# io-pack-3-1.net
KiCad netlist of a schematic drawn in EAGLE
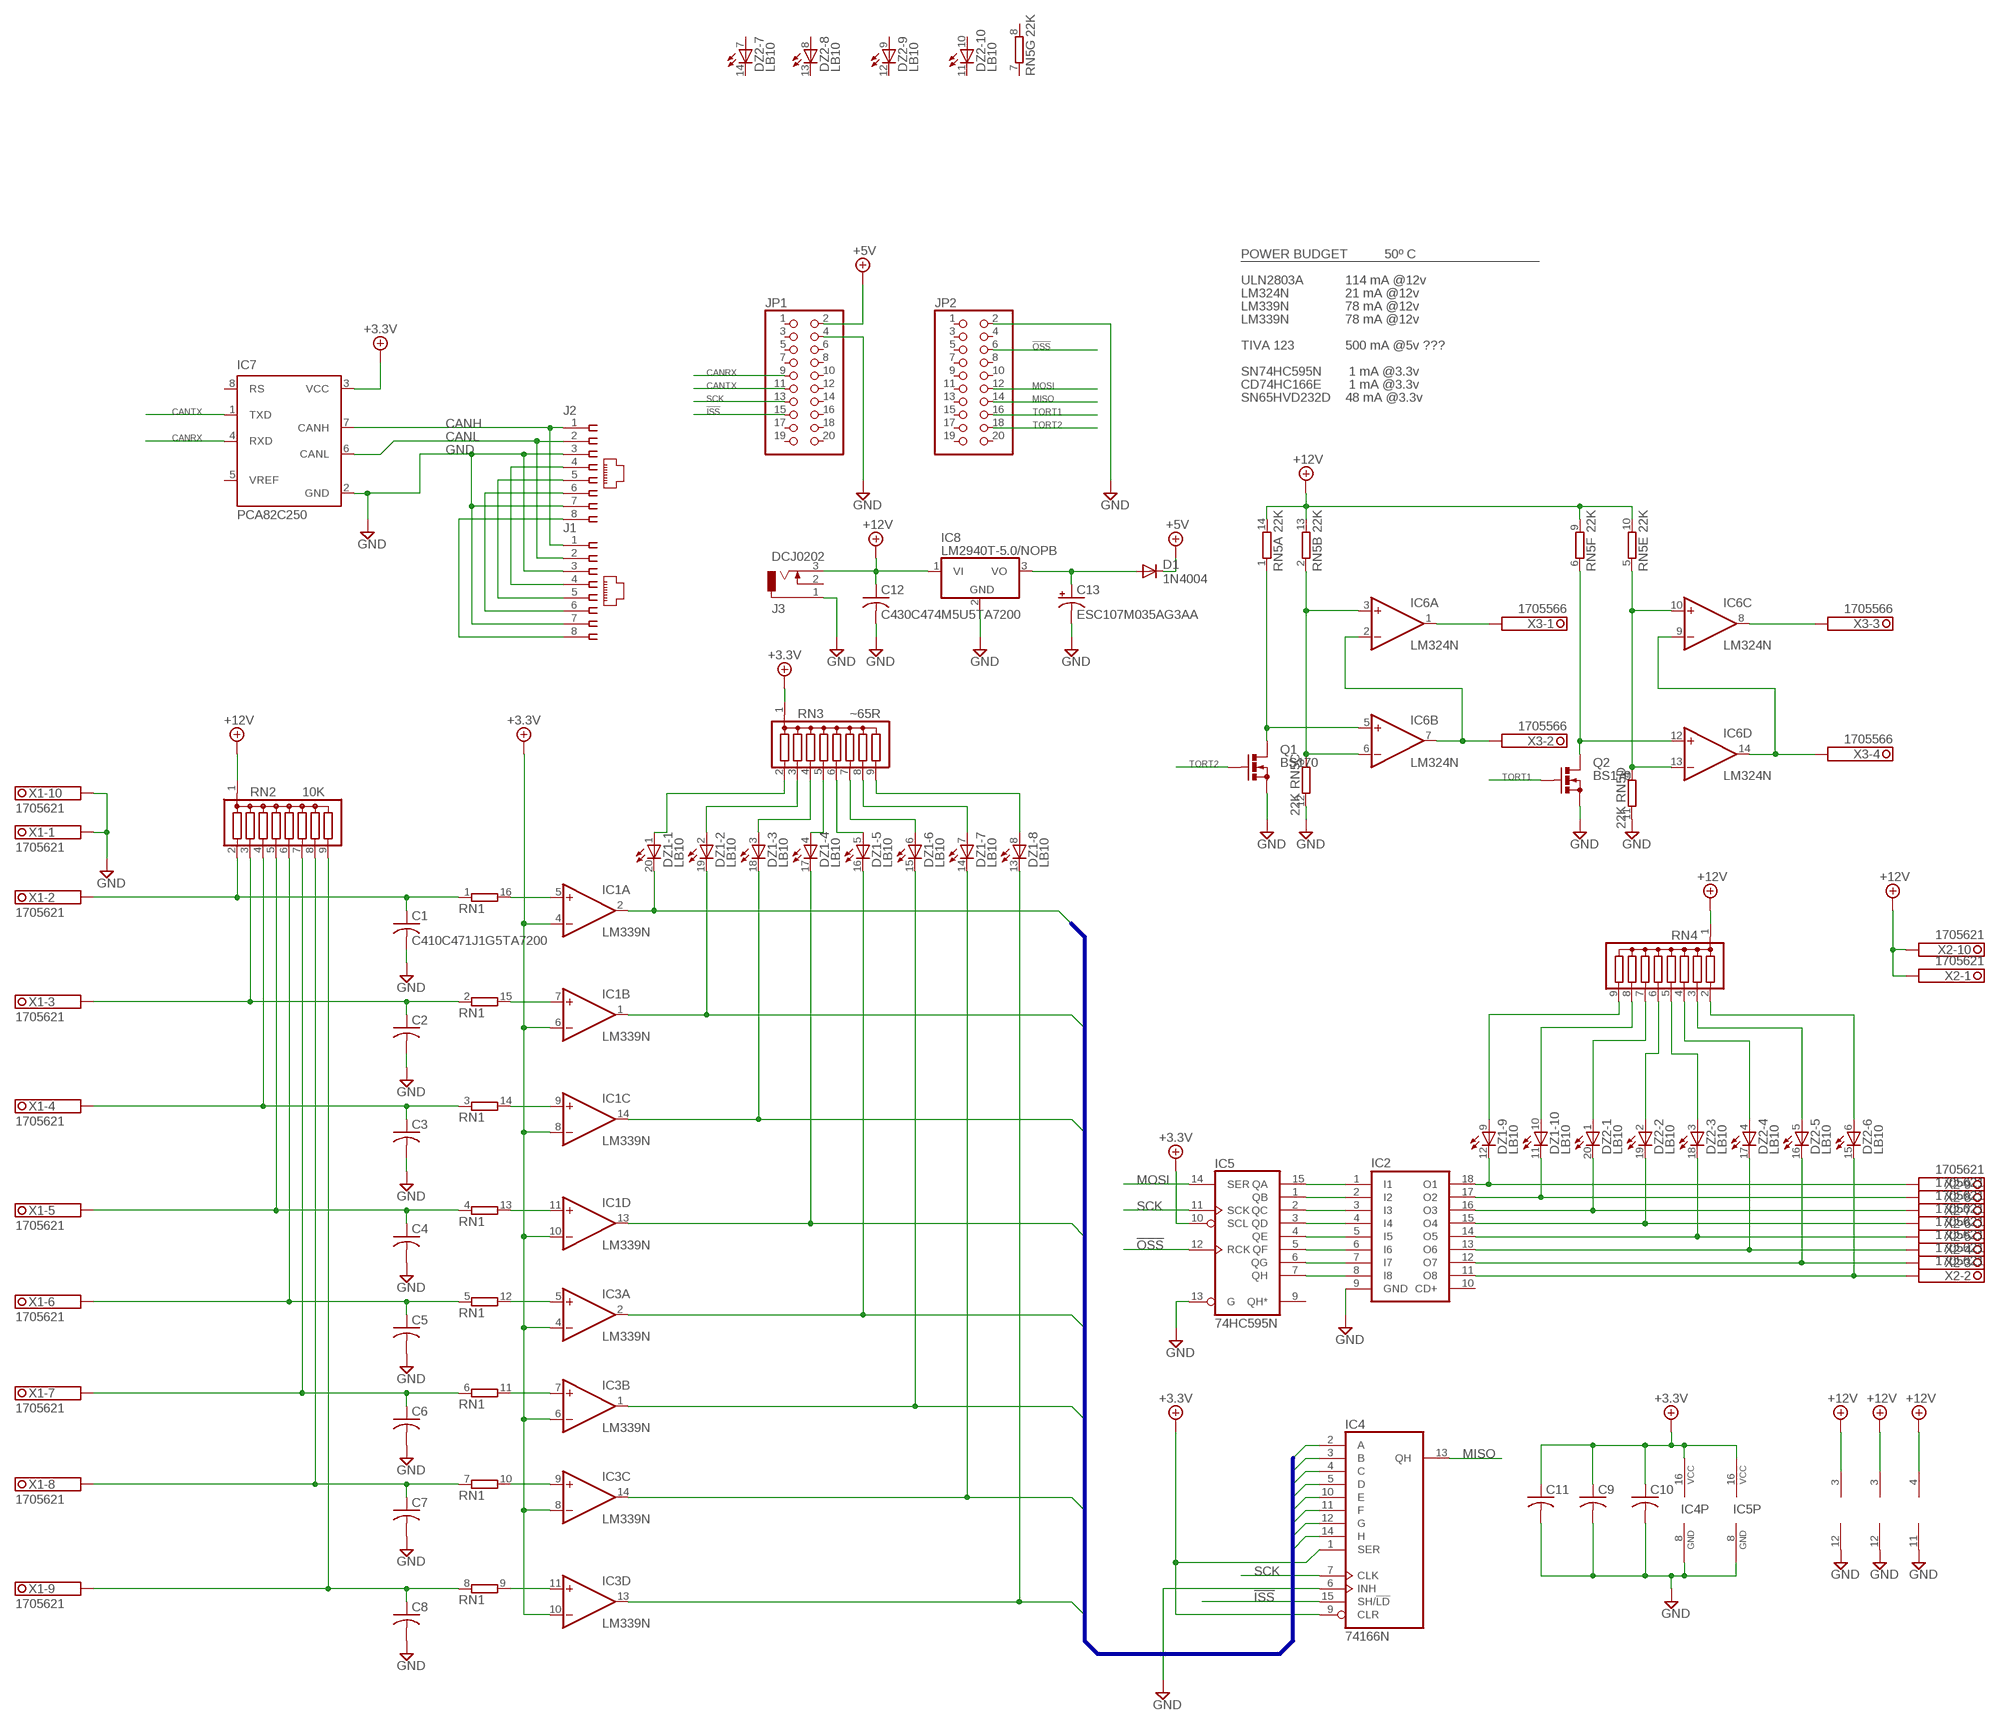
[diagram p0: schematic, sheet 1]

(export (version "E")
  (design (tool "Eeschema 10.0.6"))
  (components
    (comp (ref "C1")
      (value "C410C471J1G5TA7200")
      (footprint "eagle-import:C050-025X075")
      (libsource (lib "eagle-import") (part "C-US050-025X075"))
    )
    (comp (ref "C2")
      (value "C-US050-025X075")
      (footprint "eagle-import:C050-025X075")
      (libsource (lib "eagle-import") (part "C-US050-025X075"))
    )
    (comp (ref "C3")
      (value "C-US050-025X075")
      (footprint "eagle-import:C050-025X075")
      (libsource (lib "eagle-import") (part "C-US050-025X075"))
    )
    (comp (ref "C4")
      (value "C-US050-025X075")
      (footprint "eagle-import:C050-025X075")
      (libsource (lib "eagle-import") (part "C-US050-025X075"))
    )
    (comp (ref "C5")
      (value "C-US050-025X075")
      (footprint "eagle-import:C050-025X075")
      (libsource (lib "eagle-import") (part "C-US050-025X075"))
    )
    (comp (ref "C6")
      (value "C-US050-025X075")
      (footprint "eagle-import:C050-025X075")
      (libsource (lib "eagle-import") (part "C-US050-025X075"))
    )
    (comp (ref "C7")
      (value "C-US050-025X075")
      (footprint "eagle-import:C050-025X075")
      (libsource (lib "eagle-import") (part "C-US050-025X075"))
    )
    (comp (ref "C8")
      (value "C-US050-025X075")
      (footprint "eagle-import:C050-025X075")
      (libsource (lib "eagle-import") (part "C-US050-025X075"))
    )
    (comp (ref "C9")
      (value "C-US050-025X075")
      (footprint "eagle-import:C050-025X075")
      (libsource (lib "eagle-import") (part "C-US050-025X075"))
    )
    (comp (ref "C10")
      (value "C-US050-025X075")
      (footprint "eagle-import:C050-025X075")
      (libsource (lib "eagle-import") (part "C-US050-025X075"))
    )
    (comp (ref "C11")
      (value "C-US050-025X075")
      (footprint "eagle-import:C050-025X075")
      (libsource (lib "eagle-import") (part "C-US050-025X075"))
    )
    (comp (ref "C12")
      (value "C430C474M5U5TA7200")
      (footprint "eagle-import:C075-032X103")
      (libsource (lib "eagle-import") (part "C-US075-032X103"))
    )
    (comp (ref "C13")
      (value "ESC107M035AG3AA")
      (footprint "eagle-import:E3,5-8")
      (libsource (lib "eagle-import") (part "CPOL-USE3.5-8"))
    )
    (comp (ref "D1")
      (value "1N4004")
      (footprint "eagle-import:DO41-10")
      (libsource (lib "eagle-import") (part "1N4004"))
    )
    (comp (ref "DZ1")
      (value "LB10")
      (footprint "eagle-import:LB10")
      (libsource (lib "eagle-import") (part "LB10"))
    )
    (comp (ref "DZ2")
      (value "LB10")
      (footprint "eagle-import:LB10")
      (libsource (lib "eagle-import") (part "LB10"))
    )
    (comp (ref "IC1")
      (value "LM339N")
      (footprint "eagle-import:DIL14")
      (libsource (lib "eagle-import") (part "LM339N"))
    )
    (comp (ref "IC2")
      (value "ULN2803A")
      (footprint "eagle-import:DIL18")
      (libsource (lib "eagle-import") (part "ULN2803A"))
    )
    (comp (ref "IC3")
      (value "LM339N")
      (footprint "eagle-import:DIL14")
      (libsource (lib "eagle-import") (part "LM339N"))
    )
    (comp (ref "IC4")
      (value "74166N")
      (footprint "eagle-import:DIL16")
      (libsource (lib "eagle-import") (part "74166N"))
    )
    (comp (ref "IC5")
      (value "74HC595N")
      (footprint "eagle-import:DIL16")
      (libsource (lib "eagle-import") (part "74595NLS"))
    )
    (comp (ref "IC6")
      (value "LM324N")
      (footprint "eagle-import:DIL14")
      (libsource (lib "eagle-import") (part "LM324N"))
    )
    (comp (ref "IC7")
      (value "PCA82C250")
      (footprint "eagle-import:DIL08")
      (libsource (lib "eagle-import") (part "PCA82C250"))
    )
    (comp (ref "IC8")
      (value "LM2940T-5.0/NOPB")
      (footprint "eagle-import:TO220V")
      (libsource (lib "eagle-import") (part "78TV05"))
    )
    (comp (ref "J1")
      (value "555164-1")
      (footprint "eagle-import:555164-1")
      (libsource (lib "eagle-import") (part "555164-1"))
    )
    (comp (ref "J2")
      (value "555164-1")
      (footprint "eagle-import:555164-1")
      (libsource (lib "eagle-import") (part "555164-1"))
    )
    (comp (ref "J3")
      (value "DCJ0202")
      (footprint "eagle-import:DCJ0202")
      (libsource (lib "eagle-import") (part "DCJ0202"))
    )
    (comp (ref "JP1")
      (value "PINHD-2X10")
      (footprint "eagle-import:2X10")
      (libsource (lib "eagle-import") (part "PINHD-2X10"))
    )
    (comp (ref "JP2")
      (value "PINHD-2X10")
      (footprint "eagle-import:2X10")
      (libsource (lib "eagle-import") (part "PINHD-2X10"))
    )
    (comp (ref "Q1")
      (value "BS170")
      (footprint "eagle-import:SOT54E")
      (libsource (lib "eagle-import") (part "BS170"))
    )
    (comp (ref "Q2")
      (value "BS170")
      (footprint "eagle-import:SOT54E")
      (libsource (lib "eagle-import") (part "BS170"))
    )
    (comp (ref "RN1")
      (value "8R-P")
      (footprint "eagle-import:DIL16")
      (libsource (lib "eagle-import") (part "8R-P"))
    )
    (comp (ref "RN2")
      (value "10K")
      (footprint "eagle-import:SIL9")
      (libsource (lib "eagle-import") (part "G08R"))
    )
    (comp (ref "RN3")
      (value "~65R")
      (footprint "eagle-import:SIL9")
      (libsource (lib "eagle-import") (part "G08R"))
    )
    (comp (ref "RN4")
      (value "G08R")
      (footprint "eagle-import:SIL9")
      (libsource (lib "eagle-import") (part "G08R"))
    )
    (comp (ref "RN5")
      (value "22K")
      (footprint "eagle-import:DIL14")
      (libsource (lib "eagle-import") (part "7R-N"))
    )
    (comp (ref "X1")
      (value "1705621")
      (footprint "eagle-import:1705621")
      (libsource (lib "eagle-import") (part "1705621"))
    )
    (comp (ref "X2")
      (value "1705621")
      (footprint "eagle-import:1705621")
      (libsource (lib "eagle-import") (part "1705621"))
    )
    (comp (ref "X3")
      (value "1705566")
      (footprint "eagle-import:1705566")
      (libsource (lib "eagle-import") (part "1705566"))
    )
  )
  (nets
    (net (code "1") (name "+3.3V") (class "Default")
      (node (ref "C10") (pin "1") (pinfunction "1_1") (pintype "passive"))
      (node (ref "C11") (pin "1") (pinfunction "1_1") (pintype "passive"))
      (node (ref "C9") (pin "1") (pinfunction "1_1") (pintype "passive"))
      (node (ref "IC1") (pin "10") (pinfunction "-IN_10") (pintype "input"))
      (node (ref "IC1") (pin "4") (pinfunction "-IN_4") (pintype "input"))
      (node (ref "IC1") (pin "6") (pinfunction "-IN_6") (pintype "input"))
      (node (ref "IC1") (pin "8") (pinfunction "-IN_8") (pintype "input"))
      (node (ref "IC3") (pin "10") (pinfunction "-IN_10") (pintype "input"))
      (node (ref "IC3") (pin "4") (pinfunction "-IN_4") (pintype "input"))
      (node (ref "IC3") (pin "6") (pinfunction "-IN_6") (pintype "input"))
      (node (ref "IC3") (pin "8") (pinfunction "-IN_8") (pintype "input"))
      (node (ref "IC4") (pin "1") (pinfunction "SER_1") (pintype "input"))
      (node (ref "IC4") (pin "16") (pinfunction "VCC_16") (pintype "power_in"))
      (node (ref "IC4") (pin "9") (pinfunction "CLR_9") (pintype "input"))
      (node (ref "IC5") (pin "10") (pinfunction "SCL_10") (pintype "input"))
      (node (ref "IC5") (pin "16") (pinfunction "VCC_16") (pintype "power_in"))
      (node (ref "IC7") (pin "3") (pinfunction "VCC_3") (pintype "power_in"))
      (node (ref "RN3") (pin "1") (pinfunction "1_1") (pintype "passive"))
    )
    (net (code "2") (name "+5V") (class "Default")
      (node (ref "D1") (pin "C") (pinfunction "C_C") (pintype "passive"))
      (node (ref "JP1") (pin "2") (pinfunction "2_2") (pintype "passive"))
    )
    (net (code "3") (name "+12V") (class "Default")
      (node (ref "C12") (pin "1") (pinfunction "1_1") (pintype "passive"))
      (node (ref "IC1") (pin "3") (pinfunction "V+_3") (pintype "power_in"))
      (node (ref "IC3") (pin "3") (pinfunction "V+_3") (pintype "power_in"))
      (node (ref "IC6") (pin "4") (pinfunction "V+_4") (pintype "power_in"))
      (node (ref "IC8") (pin "1") (pinfunction "VI_1") (pintype "input"))
      (node (ref "J3") (pin "3") (pinfunction "3_3") (pintype "passive"))
      (node (ref "RN2") (pin "1") (pinfunction "1_1") (pintype "passive"))
      (node (ref "RN4") (pin "1") (pinfunction "1_1") (pintype "passive"))
      (node (ref "RN5") (pin "10") (pinfunction "2_10") (pintype "passive"))
      (node (ref "RN5") (pin "13") (pinfunction "2_13") (pintype "passive"))
      (node (ref "RN5") (pin "14") (pinfunction "2_14") (pintype "passive"))
      (node (ref "RN5") (pin "9") (pinfunction "2_9") (pintype "passive"))
      (node (ref "X2") (pin "1.1") (pinfunction "1A_1.1") (pintype "passive"))
      (node (ref "X2") (pin "1.2") (pinfunction "1A_1.2") (pintype "passive"))
      (node (ref "X2") (pin "10.1") (pinfunction "1A_10.1") (pintype "passive"))
      (node (ref "X2") (pin "10.2") (pinfunction "1A_10.2") (pintype "passive"))
    )
    (net (code "4") (name "/CANH") (class "Default")
      (node (ref "IC7") (pin "7") (pinfunction "CANH_7") (pintype "bidirectional"))
      (node (ref "J1") (pin "1") (pinfunction "1_1") (pintype "passive"))
      (node (ref "J2") (pin "1") (pinfunction "1_1") (pintype "passive"))
    )
    (net (code "5") (name "/CANL") (class "Default")
      (node (ref "IC7") (pin "6") (pinfunction "CANL_6") (pintype "bidirectional"))
      (node (ref "J1") (pin "2") (pinfunction "2_2") (pintype "passive"))
      (node (ref "J2") (pin "2") (pinfunction "2_2") (pintype "passive"))
    )
    (net (code "6") (name "/CANRX") (class "Default")
      (node (ref "IC7") (pin "4") (pinfunction "RXD_4") (pintype "output"))
      (node (ref "JP1") (pin "9") (pinfunction "9_9") (pintype "passive"))
    )
    (net (code "7") (name "/CANTX") (class "Default")
      (node (ref "IC7") (pin "1") (pinfunction "TXD_1") (pintype "input"))
      (node (ref "JP1") (pin "11") (pinfunction "11_11") (pintype "passive"))
    )
    (net (code "8") (name "/IN0") (class "Default")
      (node (ref "DZ1") (pin "20") (pinfunction "C_20") (pintype "passive"))
      (node (ref "IC1") (pin "2") (pinfunction "OUT_2") (pintype "open_collector"))
      (node (ref "IC4") (pin "2") (pinfunction "A_2") (pintype "input"))
    )
    (net (code "9") (name "/IN1") (class "Default")
      (node (ref "DZ1") (pin "19") (pinfunction "C_19") (pintype "passive"))
      (node (ref "IC1") (pin "1") (pinfunction "OUT_1") (pintype "open_collector"))
      (node (ref "IC4") (pin "3") (pinfunction "B_3") (pintype "input"))
    )
    (net (code "10") (name "/IN2") (class "Default")
      (node (ref "DZ1") (pin "18") (pinfunction "C_18") (pintype "passive"))
      (node (ref "IC1") (pin "14") (pinfunction "OUT_14") (pintype "open_collector"))
      (node (ref "IC4") (pin "4") (pinfunction "C_4") (pintype "input"))
    )
    (net (code "11") (name "/IN3") (class "Default")
      (node (ref "DZ1") (pin "17") (pinfunction "C_17") (pintype "passive"))
      (node (ref "IC1") (pin "13") (pinfunction "OUT_13") (pintype "open_collector"))
      (node (ref "IC4") (pin "5") (pinfunction "D_5") (pintype "input"))
    )
    (net (code "12") (name "/IN4") (class "Default")
      (node (ref "DZ1") (pin "16") (pinfunction "C_16") (pintype "passive"))
      (node (ref "IC3") (pin "2") (pinfunction "OUT_2") (pintype "open_collector"))
      (node (ref "IC4") (pin "10") (pinfunction "E_10") (pintype "input"))
    )
    (net (code "13") (name "/IN5") (class "Default")
      (node (ref "DZ1") (pin "15") (pinfunction "C_15") (pintype "passive"))
      (node (ref "IC3") (pin "1") (pinfunction "OUT_1") (pintype "open_collector"))
      (node (ref "IC4") (pin "11") (pinfunction "F_11") (pintype "input"))
    )
    (net (code "14") (name "/IN6") (class "Default")
      (node (ref "DZ1") (pin "14") (pinfunction "C_14") (pintype "passive"))
      (node (ref "IC3") (pin "14") (pinfunction "OUT_14") (pintype "open_collector"))
      (node (ref "IC4") (pin "12") (pinfunction "G_12") (pintype "input"))
    )
    (net (code "15") (name "/IN7") (class "Default")
      (node (ref "DZ1") (pin "13") (pinfunction "C_13") (pintype "passive"))
      (node (ref "IC3") (pin "13") (pinfunction "OUT_13") (pintype "open_collector"))
      (node (ref "IC4") (pin "14") (pinfunction "H_14") (pintype "input"))
    )
    (net (code "16") (name "/MISO") (class "Default")
      (node (ref "IC4") (pin "13") (pinfunction "QH_13") (pintype "output"))
      (node (ref "JP2") (pin "14") (pinfunction "14_14") (pintype "passive"))
    )
    (net (code "17") (name "/MOSI") (class "Default")
      (node (ref "IC5") (pin "14") (pinfunction "SER_14") (pintype "input"))
      (node (ref "JP2") (pin "12") (pinfunction "12_12") (pintype "passive"))
    )
    (net (code "18") (name "/SCK") (class "Default")
      (node (ref "IC4") (pin "7") (pinfunction "CLK_7") (pintype "input"))
      (node (ref "IC5") (pin "11") (pinfunction "SCK_11") (pintype "input"))
      (node (ref "JP1") (pin "13") (pinfunction "13_13") (pintype "passive"))
    )
    (net (code "19") (name "/TORT1") (class "Default")
      (node (ref "JP2") (pin "16") (pinfunction "16_16") (pintype "passive"))
      (node (ref "Q2") (pin "G") (pinfunction "G_G") (pintype "passive"))
    )
    (net (code "20") (name "/TORT2") (class "Default")
      (node (ref "JP2") (pin "18") (pinfunction "18_18") (pintype "passive"))
      (node (ref "Q1") (pin "G") (pinfunction "G_G") (pintype "passive"))
    )
    (net (code "21") (name "/~{ISS}") (class "Default")
      (node (ref "IC4") (pin "15") (pinfunction "SH/~{LD}_15") (pintype "input"))
      (node (ref "JP1") (pin "15") (pinfunction "15_15") (pintype "passive"))
    )
    (net (code "22") (name "/~{OSS}") (class "Default")
      (node (ref "IC5") (pin "12") (pinfunction "RCK_12") (pintype "input"))
      (node (ref "JP2") (pin "6") (pinfunction "6_6") (pintype "passive"))
    )
    (net (code "23") (name "GND") (class "Default")
      (node (ref "C1") (pin "2") (pinfunction "2_2") (pintype "passive"))
      (node (ref "C10") (pin "2") (pinfunction "2_2") (pintype "passive"))
      (node (ref "C11") (pin "2") (pinfunction "2_2") (pintype "passive"))
      (node (ref "C12") (pin "2") (pinfunction "2_2") (pintype "passive"))
      (node (ref "C13") (pin "-") (pinfunction "-_-") (pintype "passive"))
      (node (ref "C2") (pin "2") (pinfunction "2_2") (pintype "passive"))
      (node (ref "C3") (pin "2") (pinfunction "2_2") (pintype "passive"))
      (node (ref "C4") (pin "2") (pinfunction "2_2") (pintype "passive"))
      (node (ref "C5") (pin "2") (pinfunction "2_2") (pintype "passive"))
      (node (ref "C6") (pin "2") (pinfunction "2_2") (pintype "passive"))
      (node (ref "C7") (pin "2") (pinfunction "2_2") (pintype "passive"))
      (node (ref "C8") (pin "2") (pinfunction "2_2") (pintype "passive"))
      (node (ref "C9") (pin "2") (pinfunction "2_2") (pintype "passive"))
      (node (ref "IC1") (pin "12") (pinfunction "GND_12") (pintype "power_in"))
      (node (ref "IC2") (pin "9") (pinfunction "GND_9") (pintype "power_in"))
      (node (ref "IC3") (pin "12") (pinfunction "GND_12") (pintype "power_in"))
      (node (ref "IC4") (pin "6") (pinfunction "INH_6") (pintype "input"))
      (node (ref "IC4") (pin "8") (pinfunction "GND_8") (pintype "power_in"))
      (node (ref "IC5") (pin "13") (pinfunction "G_13") (pintype "input"))
      (node (ref "IC5") (pin "8") (pinfunction "GND_8") (pintype "power_in"))
      (node (ref "IC6") (pin "11") (pinfunction "V-_11") (pintype "power_in"))
      (node (ref "IC7") (pin "2") (pinfunction "GND_2") (pintype "power_in"))
      (node (ref "IC8") (pin "2") (pinfunction "GND_2") (pintype "passive"))
      (node (ref "J1") (pin "3") (pinfunction "3_3") (pintype "passive"))
      (node (ref "J1") (pin "7") (pinfunction "7_7") (pintype "passive"))
      (node (ref "J2") (pin "3") (pinfunction "3_3") (pintype "passive"))
      (node (ref "J2") (pin "7") (pinfunction "7_7") (pintype "passive"))
      (node (ref "J3") (pin "1") (pinfunction "1_1") (pintype "passive"))
      (node (ref "JP1") (pin "4") (pinfunction "4_4") (pintype "passive"))
      (node (ref "JP2") (pin "2") (pinfunction "2_2") (pintype "passive"))
      (node (ref "Q1") (pin "S") (pinfunction "S_S") (pintype "passive"))
      (node (ref "Q2") (pin "S") (pinfunction "S_S") (pintype "passive"))
      (node (ref "RN5") (pin "11") (pinfunction "2_11") (pintype "passive"))
      (node (ref "RN5") (pin "12") (pinfunction "2_12") (pintype "passive"))
      (node (ref "X1") (pin "1.1") (pinfunction "1A_1.1") (pintype "passive"))
      (node (ref "X1") (pin "1.2") (pinfunction "1A_1.2") (pintype "passive"))
      (node (ref "X1") (pin "10.1") (pinfunction "1A_10.1") (pintype "passive"))
      (node (ref "X1") (pin "10.2") (pinfunction "1A_10.2") (pintype "passive"))
    )
    (net (code "24") (name "Net-(C1-Pad1)") (class "Default")
      (node (ref "C1") (pin "1") (pinfunction "1_1") (pintype "passive"))
      (node (ref "RN1") (pin "1") (pinfunction "1_1") (pintype "passive"))
      (node (ref "RN2") (pin "2") (pinfunction "2_2") (pintype "passive"))
      (node (ref "X1") (pin "2.1") (pinfunction "1A_2.1") (pintype "passive"))
      (node (ref "X1") (pin "2.2") (pinfunction "1A_2.2") (pintype "passive"))
    )
    (net (code "25") (name "Net-(DZ1A-A)") (class "Default")
      (node (ref "DZ1") (pin "1") (pinfunction "A_1") (pintype "passive"))
      (node (ref "RN3") (pin "2") (pinfunction "2_2") (pintype "passive"))
    )
    (net (code "26") (name "Net-(DZ1B-A)") (class "Default")
      (node (ref "DZ1") (pin "10") (pinfunction "A_10") (pintype "passive"))
      (node (ref "RN4") (pin "8") (pinfunction "8_8") (pintype "passive"))
    )
    (net (code "27") (name "Net-(DZ1B-C)") (class "Default")
      (node (ref "DZ1") (pin "11") (pinfunction "C_11") (pintype "passive"))
      (node (ref "IC2") (pin "17") (pinfunction "O2_17") (pintype "open_collector"))
      (node (ref "X2") (pin "8.1") (pinfunction "1A_8.1") (pintype "passive"))
      (node (ref "X2") (pin "8.2") (pinfunction "1A_8.2") (pintype "passive"))
    )
    (net (code "28") (name "Net-(DZ1C-A)") (class "Default")
      (node (ref "DZ1") (pin "2") (pinfunction "A_2") (pintype "passive"))
      (node (ref "RN3") (pin "3") (pinfunction "3_3") (pintype "passive"))
    )
    (net (code "29") (name "Net-(DZ1D-A)") (class "Default")
      (node (ref "DZ1") (pin "3") (pinfunction "A_3") (pintype "passive"))
      (node (ref "RN3") (pin "4") (pinfunction "4_4") (pintype "passive"))
    )
    (net (code "30") (name "Net-(DZ1E-A)") (class "Default")
      (node (ref "DZ1") (pin "4") (pinfunction "A_4") (pintype "passive"))
      (node (ref "RN3") (pin "5") (pinfunction "5_5") (pintype "passive"))
    )
    (net (code "31") (name "Net-(DZ1F-A)") (class "Default")
      (node (ref "DZ1") (pin "5") (pinfunction "A_5") (pintype "passive"))
      (node (ref "RN3") (pin "6") (pinfunction "6_6") (pintype "passive"))
    )
    (net (code "32") (name "Net-(DZ1G-A)") (class "Default")
      (node (ref "DZ1") (pin "6") (pinfunction "A_6") (pintype "passive"))
      (node (ref "RN3") (pin "7") (pinfunction "7_7") (pintype "passive"))
    )
    (net (code "33") (name "Net-(DZ1H-A)") (class "Default")
      (node (ref "DZ1") (pin "7") (pinfunction "A_7") (pintype "passive"))
      (node (ref "RN3") (pin "8") (pinfunction "8_8") (pintype "passive"))
    )
    (net (code "34") (name "Net-(DZ1I-A)") (class "Default")
      (node (ref "DZ1") (pin "8") (pinfunction "A_8") (pintype "passive"))
      (node (ref "RN3") (pin "9") (pinfunction "9_9") (pintype "passive"))
    )
    (net (code "35") (name "Net-(DZ1J-A)") (class "Default")
      (node (ref "DZ1") (pin "9") (pinfunction "A_9") (pintype "passive"))
      (node (ref "RN4") (pin "9") (pinfunction "9_9") (pintype "passive"))
    )
    (net (code "36") (name "Net-(DZ1J-C)") (class "Default")
      (node (ref "DZ1") (pin "12") (pinfunction "C_12") (pintype "passive"))
      (node (ref "IC2") (pin "18") (pinfunction "O1_18") (pintype "open_collector"))
      (node (ref "X2") (pin "9.1") (pinfunction "1A_9.1") (pintype "passive"))
      (node (ref "X2") (pin "9.2") (pinfunction "1A_9.2") (pintype "passive"))
    )
    (net (code "37") (name "Net-(DZ2A-A)") (class "Default")
      (node (ref "DZ2") (pin "1") (pinfunction "A_1") (pintype "passive"))
      (node (ref "RN4") (pin "7") (pinfunction "7_7") (pintype "passive"))
    )
    (net (code "38") (name "Net-(DZ2A-C)") (class "Default")
      (node (ref "DZ2") (pin "20") (pinfunction "C_20") (pintype "passive"))
      (node (ref "IC2") (pin "16") (pinfunction "O3_16") (pintype "open_collector"))
      (node (ref "X2") (pin "7.1") (pinfunction "1A_7.1") (pintype "passive"))
      (node (ref "X2") (pin "7.2") (pinfunction "1A_7.2") (pintype "passive"))
    )
    (net (code "39") (name "Net-(DZ2C-A)") (class "Default")
      (node (ref "DZ2") (pin "2") (pinfunction "A_2") (pintype "passive"))
      (node (ref "RN4") (pin "6") (pinfunction "6_6") (pintype "passive"))
    )
    (net (code "40") (name "Net-(DZ2C-C)") (class "Default")
      (node (ref "DZ2") (pin "19") (pinfunction "C_19") (pintype "passive"))
      (node (ref "IC2") (pin "15") (pinfunction "O4_15") (pintype "open_collector"))
      (node (ref "X2") (pin "6.1") (pinfunction "1A_6.1") (pintype "passive"))
      (node (ref "X2") (pin "6.2") (pinfunction "1A_6.2") (pintype "passive"))
    )
    (net (code "41") (name "Net-(DZ2D-A)") (class "Default")
      (node (ref "DZ2") (pin "3") (pinfunction "A_3") (pintype "passive"))
      (node (ref "RN4") (pin "5") (pinfunction "5_5") (pintype "passive"))
    )
    (net (code "42") (name "Net-(DZ2D-C)") (class "Default")
      (node (ref "DZ2") (pin "18") (pinfunction "C_18") (pintype "passive"))
      (node (ref "IC2") (pin "14") (pinfunction "O5_14") (pintype "open_collector"))
      (node (ref "X2") (pin "5.1") (pinfunction "1A_5.1") (pintype "passive"))
      (node (ref "X2") (pin "5.2") (pinfunction "1A_5.2") (pintype "passive"))
    )
    (net (code "43") (name "Net-(DZ2E-A)") (class "Default")
      (node (ref "DZ2") (pin "4") (pinfunction "A_4") (pintype "passive"))
      (node (ref "RN4") (pin "4") (pinfunction "4_4") (pintype "passive"))
    )
    (net (code "44") (name "Net-(DZ2E-C)") (class "Default")
      (node (ref "DZ2") (pin "17") (pinfunction "C_17") (pintype "passive"))
      (node (ref "IC2") (pin "13") (pinfunction "O6_13") (pintype "open_collector"))
      (node (ref "X2") (pin "4.1") (pinfunction "1A_4.1") (pintype "passive"))
      (node (ref "X2") (pin "4.2") (pinfunction "1A_4.2") (pintype "passive"))
    )
    (net (code "45") (name "Net-(DZ2F-A)") (class "Default")
      (node (ref "DZ2") (pin "5") (pinfunction "A_5") (pintype "passive"))
      (node (ref "RN4") (pin "3") (pinfunction "3_3") (pintype "passive"))
    )
    (net (code "46") (name "Net-(DZ2F-C)") (class "Default")
      (node (ref "DZ2") (pin "16") (pinfunction "C_16") (pintype "passive"))
      (node (ref "IC2") (pin "12") (pinfunction "O7_12") (pintype "open_collector"))
      (node (ref "X2") (pin "3.1") (pinfunction "1A_3.1") (pintype "passive"))
      (node (ref "X2") (pin "3.2") (pinfunction "1A_3.2") (pintype "passive"))
    )
    (net (code "47") (name "Net-(DZ2G-A)") (class "Default")
      (node (ref "DZ2") (pin "6") (pinfunction "A_6") (pintype "passive"))
      (node (ref "RN4") (pin "2") (pinfunction "2_2") (pintype "passive"))
    )
    (net (code "48") (name "Net-(DZ2G-C)") (class "Default")
      (node (ref "DZ2") (pin "15") (pinfunction "C_15") (pintype "passive"))
      (node (ref "IC2") (pin "11") (pinfunction "O8_11") (pintype "open_collector"))
      (node (ref "X2") (pin "2.1") (pinfunction "1A_2.1") (pintype "passive"))
      (node (ref "X2") (pin "2.2") (pinfunction "1A_2.2") (pintype "passive"))
    )
    (net (code "49") (name "Net-(IC1A-+IN)") (class "Default")
      (node (ref "IC1") (pin "5") (pinfunction "+IN_5") (pintype "input"))
      (node (ref "RN1") (pin "16") (pinfunction "2_16") (pintype "passive"))
    )
    (net (code "50") (name "Net-(IC1B-+IN)") (class "Default")
      (node (ref "IC1") (pin "7") (pinfunction "+IN_7") (pintype "input"))
      (node (ref "RN1") (pin "15") (pinfunction "2_15") (pintype "passive"))
    )
    (net (code "51") (name "Net-(IC1C-+IN)") (class "Default")
      (node (ref "IC1") (pin "9") (pinfunction "+IN_9") (pintype "input"))
      (node (ref "RN1") (pin "14") (pinfunction "2_14") (pintype "passive"))
    )
    (net (code "52") (name "Net-(IC1D-+IN)") (class "Default")
      (node (ref "IC1") (pin "11") (pinfunction "+IN_11") (pintype "input"))
      (node (ref "RN1") (pin "13") (pinfunction "2_13") (pintype "passive"))
    )
    (net (code "53") (name "Net-(IC2-I1)") (class "Default")
      (node (ref "IC2") (pin "1") (pinfunction "I1_1") (pintype "input"))
      (node (ref "IC5") (pin "15") (pinfunction "QA_15") (pintype "tri_state"))
    )
    (net (code "54") (name "Net-(IC2-I2)") (class "Default")
      (node (ref "IC2") (pin "2") (pinfunction "I2_2") (pintype "input"))
      (node (ref "IC5") (pin "1") (pinfunction "QB_1") (pintype "tri_state"))
    )
    (net (code "55") (name "Net-(IC2-I3)") (class "Default")
      (node (ref "IC2") (pin "3") (pinfunction "I3_3") (pintype "input"))
      (node (ref "IC5") (pin "2") (pinfunction "QC_2") (pintype "tri_state"))
    )
    (net (code "56") (name "Net-(IC2-I4)") (class "Default")
      (node (ref "IC2") (pin "4") (pinfunction "I4_4") (pintype "input"))
      (node (ref "IC5") (pin "3") (pinfunction "QD_3") (pintype "tri_state"))
    )
    (net (code "57") (name "Net-(IC2-I5)") (class "Default")
      (node (ref "IC2") (pin "5") (pinfunction "I5_5") (pintype "input"))
      (node (ref "IC5") (pin "4") (pinfunction "QE_4") (pintype "tri_state"))
    )
    (net (code "58") (name "Net-(IC2-I6)") (class "Default")
      (node (ref "IC2") (pin "6") (pinfunction "I6_6") (pintype "input"))
      (node (ref "IC5") (pin "5") (pinfunction "QF_5") (pintype "tri_state"))
    )
    (net (code "59") (name "Net-(IC2-I7)") (class "Default")
      (node (ref "IC2") (pin "7") (pinfunction "I7_7") (pintype "input"))
      (node (ref "IC5") (pin "6") (pinfunction "QG_6") (pintype "tri_state"))
    )
    (net (code "60") (name "Net-(IC2-I8)") (class "Default")
      (node (ref "IC2") (pin "8") (pinfunction "I8_8") (pintype "input"))
      (node (ref "IC5") (pin "7") (pinfunction "QH_7") (pintype "tri_state"))
    )
    (net (code "61") (name "Net-(IC3A-+IN)") (class "Default")
      (node (ref "IC3") (pin "5") (pinfunction "+IN_5") (pintype "input"))
      (node (ref "RN1") (pin "12") (pinfunction "2_12") (pintype "passive"))
    )
    (net (code "62") (name "Net-(IC3B-+IN)") (class "Default")
      (node (ref "IC3") (pin "7") (pinfunction "+IN_7") (pintype "input"))
      (node (ref "RN1") (pin "11") (pinfunction "2_11") (pintype "passive"))
    )
    (net (code "63") (name "Net-(IC3C-+IN)") (class "Default")
      (node (ref "IC3") (pin "9") (pinfunction "+IN_9") (pintype "input"))
      (node (ref "RN1") (pin "10") (pinfunction "2_10") (pintype "passive"))
    )
    (net (code "64") (name "Net-(IC3D-+IN)") (class "Default")
      (node (ref "IC3") (pin "11") (pinfunction "+IN_11") (pintype "input"))
      (node (ref "RN1") (pin "9") (pinfunction "2_9") (pintype "passive"))
    )
    (net (code "65") (name "Net-(IC6A-+IN)") (class "Default")
      (node (ref "IC6") (pin "3") (pinfunction "+IN_3") (pintype "input"))
      (node (ref "IC6") (pin "6") (pinfunction "-IN_6") (pintype "input"))
      (node (ref "RN5") (pin "2") (pinfunction "1_2") (pintype "passive"))
      (node (ref "RN5") (pin "3") (pinfunction "1_3") (pintype "passive"))
    )
    (net (code "66") (name "Net-(IC6A--IN)") (class "Default")
      (node (ref "IC6") (pin "2") (pinfunction "-IN_2") (pintype "input"))
      (node (ref "IC6") (pin "7") (pinfunction "OUT_7") (pintype "output"))
      (node (ref "X3") (pin "2.1") (pinfunction "1A_2.1") (pintype "passive"))
      (node (ref "X3") (pin "2.2") (pinfunction "1A_2.2") (pintype "passive"))
    )
    (net (code "67") (name "Net-(IC6A-OUT)") (class "Default")
      (node (ref "IC6") (pin "1") (pinfunction "OUT_1") (pintype "output"))
      (node (ref "X3") (pin "1.1") (pinfunction "1A_1.1") (pintype "passive"))
      (node (ref "X3") (pin "1.2") (pinfunction "1A_1.2") (pintype "passive"))
    )
    (net (code "68") (name "Net-(IC6B-+IN)") (class "Default")
      (node (ref "IC6") (pin "5") (pinfunction "+IN_5") (pintype "input"))
      (node (ref "Q1") (pin "D") (pinfunction "D_D") (pintype "passive"))
      (node (ref "RN5") (pin "1") (pinfunction "1_1") (pintype "passive"))
    )
    (net (code "69") (name "Net-(IC6C-+IN)") (class "Default")
      (node (ref "IC6") (pin "10") (pinfunction "+IN_10") (pintype "input"))
      (node (ref "IC6") (pin "13") (pinfunction "-IN_13") (pintype "input"))
      (node (ref "RN5") (pin "4") (pinfunction "1_4") (pintype "passive"))
      (node (ref "RN5") (pin "5") (pinfunction "1_5") (pintype "passive"))
    )
    (net (code "70") (name "Net-(IC6C--IN)") (class "Default")
      (node (ref "IC6") (pin "14") (pinfunction "OUT_14") (pintype "output"))
      (node (ref "IC6") (pin "9") (pinfunction "-IN_9") (pintype "input"))
      (node (ref "X3") (pin "4.1") (pinfunction "1A_4.1") (pintype "passive"))
      (node (ref "X3") (pin "4.2") (pinfunction "1A_4.2") (pintype "passive"))
    )
    (net (code "71") (name "Net-(IC6C-OUT)") (class "Default")
      (node (ref "IC6") (pin "8") (pinfunction "OUT_8") (pintype "output"))
      (node (ref "X3") (pin "3.1") (pinfunction "1A_3.1") (pintype "passive"))
      (node (ref "X3") (pin "3.2") (pinfunction "1A_3.2") (pintype "passive"))
    )
    (net (code "72") (name "Net-(IC6D-+IN)") (class "Default")
      (node (ref "IC6") (pin "12") (pinfunction "+IN_12") (pintype "input"))
      (node (ref "Q2") (pin "D") (pinfunction "D_D") (pintype "passive"))
      (node (ref "RN5") (pin "6") (pinfunction "1_6") (pintype "passive"))
    )
    (net (code "73") (name "Net-(IC8-VO)") (class "Default")
      (node (ref "C13") (pin "+") (pinfunction "+_+") (pintype "passive"))
      (node (ref "D1") (pin "A") (pinfunction "A_A") (pintype "passive"))
      (node (ref "IC8") (pin "3") (pinfunction "VO_3") (pintype "passive"))
    )
    (net (code "74") (name "Net-(J1-Pad4)") (class "Default")
      (node (ref "J1") (pin "4") (pinfunction "4_4") (pintype "passive"))
      (node (ref "J2") (pin "4") (pinfunction "4_4") (pintype "passive"))
    )
    (net (code "75") (name "Net-(J1-Pad5)") (class "Default")
      (node (ref "J1") (pin "5") (pinfunction "5_5") (pintype "passive"))
      (node (ref "J2") (pin "5") (pinfunction "5_5") (pintype "passive"))
    )
    (net (code "76") (name "Net-(J1-Pad6)") (class "Default")
      (node (ref "J1") (pin "6") (pinfunction "6_6") (pintype "passive"))
      (node (ref "J2") (pin "6") (pinfunction "6_6") (pintype "passive"))
    )
    (net (code "77") (name "Net-(J1-Pad8)") (class "Default")
      (node (ref "J1") (pin "8") (pinfunction "8_8") (pintype "passive"))
      (node (ref "J2") (pin "8") (pinfunction "8_8") (pintype "passive"))
    )
    (net (code "78") (name "Net-(RN1B-1)") (class "Default")
      (node (ref "C2") (pin "1") (pinfunction "1_1") (pintype "passive"))
      (node (ref "RN1") (pin "2") (pinfunction "1_2") (pintype "passive"))
      (node (ref "RN2") (pin "3") (pinfunction "3_3") (pintype "passive"))
      (node (ref "X1") (pin "3.1") (pinfunction "1A_3.1") (pintype "passive"))
      (node (ref "X1") (pin "3.2") (pinfunction "1A_3.2") (pintype "passive"))
    )
    (net (code "79") (name "Net-(RN1C-1)") (class "Default")
      (node (ref "C3") (pin "1") (pinfunction "1_1") (pintype "passive"))
      (node (ref "RN1") (pin "3") (pinfunction "1_3") (pintype "passive"))
      (node (ref "RN2") (pin "4") (pinfunction "4_4") (pintype "passive"))
      (node (ref "X1") (pin "4.1") (pinfunction "1A_4.1") (pintype "passive"))
      (node (ref "X1") (pin "4.2") (pinfunction "1A_4.2") (pintype "passive"))
    )
    (net (code "80") (name "Net-(RN1D-1)") (class "Default")
      (node (ref "C4") (pin "1") (pinfunction "1_1") (pintype "passive"))
      (node (ref "RN1") (pin "4") (pinfunction "1_4") (pintype "passive"))
      (node (ref "RN2") (pin "5") (pinfunction "5_5") (pintype "passive"))
      (node (ref "X1") (pin "5.1") (pinfunction "1A_5.1") (pintype "passive"))
      (node (ref "X1") (pin "5.2") (pinfunction "1A_5.2") (pintype "passive"))
    )
    (net (code "81") (name "Net-(RN1E-1)") (class "Default")
      (node (ref "C5") (pin "1") (pinfunction "1_1") (pintype "passive"))
      (node (ref "RN1") (pin "5") (pinfunction "1_5") (pintype "passive"))
      (node (ref "RN2") (pin "6") (pinfunction "6_6") (pintype "passive"))
      (node (ref "X1") (pin "6.1") (pinfunction "1A_6.1") (pintype "passive"))
      (node (ref "X1") (pin "6.2") (pinfunction "1A_6.2") (pintype "passive"))
    )
    (net (code "82") (name "Net-(RN1F-1)") (class "Default")
      (node (ref "C6") (pin "1") (pinfunction "1_1") (pintype "passive"))
      (node (ref "RN1") (pin "6") (pinfunction "1_6") (pintype "passive"))
      (node (ref "RN2") (pin "7") (pinfunction "7_7") (pintype "passive"))
      (node (ref "X1") (pin "7.1") (pinfunction "1A_7.1") (pintype "passive"))
      (node (ref "X1") (pin "7.2") (pinfunction "1A_7.2") (pintype "passive"))
    )
    (net (code "83") (name "Net-(RN1G-1)") (class "Default")
      (node (ref "C7") (pin "1") (pinfunction "1_1") (pintype "passive"))
      (node (ref "RN1") (pin "7") (pinfunction "1_7") (pintype "passive"))
      (node (ref "RN2") (pin "8") (pinfunction "8_8") (pintype "passive"))
      (node (ref "X1") (pin "8.1") (pinfunction "1A_8.1") (pintype "passive"))
      (node (ref "X1") (pin "8.2") (pinfunction "1A_8.2") (pintype "passive"))
    )
    (net (code "84") (name "Net-(RN1H-1)") (class "Default")
      (node (ref "C8") (pin "1") (pinfunction "1_1") (pintype "passive"))
      (node (ref "RN1") (pin "8") (pinfunction "1_8") (pintype "passive"))
      (node (ref "RN2") (pin "9") (pinfunction "9_9") (pintype "passive"))
      (node (ref "X1") (pin "9.1") (pinfunction "1A_9.1") (pintype "passive"))
      (node (ref "X1") (pin "9.2") (pinfunction "1A_9.2") (pintype "passive"))
    )
    (net (code "85") (name "unconnected-(DZ2B-A-Pad10)") (class "Default")
      (node (ref "DZ2") (pin "10") (pinfunction "A_10") (pintype "passive"))
    )
    (net (code "86") (name "unconnected-(DZ2B-C-Pad11)") (class "Default")
      (node (ref "DZ2") (pin "11") (pinfunction "C_11") (pintype "passive"))
    )
    (net (code "87") (name "unconnected-(DZ2H-A-Pad7)") (class "Default")
      (node (ref "DZ2") (pin "7") (pinfunction "A_7") (pintype "passive"))
    )
    (net (code "88") (name "unconnected-(DZ2H-C-Pad14)") (class "Default")
      (node (ref "DZ2") (pin "14") (pinfunction "C_14") (pintype "passive"))
    )
    (net (code "89") (name "unconnected-(DZ2I-A-Pad8)") (class "Default")
      (node (ref "DZ2") (pin "8") (pinfunction "A_8") (pintype "passive"))
    )
    (net (code "90") (name "unconnected-(DZ2I-C-Pad13)") (class "Default")
      (node (ref "DZ2") (pin "13") (pinfunction "C_13") (pintype "passive"))
    )
    (net (code "91") (name "unconnected-(DZ2J-A-Pad9)") (class "Default")
      (node (ref "DZ2") (pin "9") (pinfunction "A_9") (pintype "passive"))
    )
    (net (code "92") (name "unconnected-(DZ2J-C-Pad12)") (class "Default")
      (node (ref "DZ2") (pin "12") (pinfunction "C_12") (pintype "passive"))
    )
    (net (code "93") (name "unconnected-(IC2-CD+-Pad10)") (class "Default")
      (node (ref "IC2") (pin "10") (pinfunction "CD+_10") (pintype "passive"))
    )
    (net (code "94") (name "unconnected-(IC5A-QH*-Pad9)") (class "Default")
      (node (ref "IC5") (pin "9") (pinfunction "QH*_9") (pintype "tri_state"))
    )
    (net (code "95") (name "unconnected-(IC7-RS-Pad8)") (class "Default")
      (node (ref "IC7") (pin "8") (pinfunction "RS_8") (pintype "input"))
    )
    (net (code "96") (name "unconnected-(IC7-VREF-Pad5)") (class "Default")
      (node (ref "IC7") (pin "5") (pinfunction "VREF_5") (pintype "output"))
    )
    (net (code "97") (name "unconnected-(J3-Pad2)") (class "Default")
      (node (ref "J3") (pin "2") (pinfunction "2_2") (pintype "passive"))
    )
    (net (code "98") (name "unconnected-(JP1-Pad1)") (class "Default")
      (node (ref "JP1") (pin "1") (pinfunction "1_1") (pintype "passive"))
    )
    (net (code "99") (name "unconnected-(JP1-Pad3)") (class "Default")
      (node (ref "JP1") (pin "3") (pinfunction "3_3") (pintype "passive"))
    )
    (net (code "100") (name "unconnected-(JP1-Pad5)") (class "Default")
      (node (ref "JP1") (pin "5") (pinfunction "5_5") (pintype "passive"))
    )
    (net (code "101") (name "unconnected-(JP1-Pad6)") (class "Default")
      (node (ref "JP1") (pin "6") (pinfunction "6_6") (pintype "passive"))
    )
    (net (code "102") (name "unconnected-(JP1-Pad7)") (class "Default")
      (node (ref "JP1") (pin "7") (pinfunction "7_7") (pintype "passive"))
    )
    (net (code "103") (name "unconnected-(JP1-Pad8)") (class "Default")
      (node (ref "JP1") (pin "8") (pinfunction "8_8") (pintype "passive"))
    )
    (net (code "104") (name "unconnected-(JP1-Pad10)") (class "Default")
      (node (ref "JP1") (pin "10") (pinfunction "10_10") (pintype "passive"))
    )
    (net (code "105") (name "unconnected-(JP1-Pad12)") (class "Default")
      (node (ref "JP1") (pin "12") (pinfunction "12_12") (pintype "passive"))
    )
    (net (code "106") (name "unconnected-(JP1-Pad14)") (class "Default")
      (node (ref "JP1") (pin "14") (pinfunction "14_14") (pintype "passive"))
    )
    (net (code "107") (name "unconnected-(JP1-Pad16)") (class "Default")
      (node (ref "JP1") (pin "16") (pinfunction "16_16") (pintype "passive"))
    )
    (net (code "108") (name "unconnected-(JP1-Pad17)") (class "Default")
      (node (ref "JP1") (pin "17") (pinfunction "17_17") (pintype "passive"))
    )
    (net (code "109") (name "unconnected-(JP1-Pad18)") (class "Default")
      (node (ref "JP1") (pin "18") (pinfunction "18_18") (pintype "passive"))
    )
    (net (code "110") (name "unconnected-(JP1-Pad19)") (class "Default")
      (node (ref "JP1") (pin "19") (pinfunction "19_19") (pintype "passive"))
    )
    (net (code "111") (name "unconnected-(JP1-Pad20)") (class "Default")
      (node (ref "JP1") (pin "20") (pinfunction "20_20") (pintype "passive"))
    )
    (net (code "112") (name "unconnected-(JP2-Pad1)") (class "Default")
      (node (ref "JP2") (pin "1") (pinfunction "1_1") (pintype "passive"))
    )
    (net (code "113") (name "unconnected-(JP2-Pad3)") (class "Default")
      (node (ref "JP2") (pin "3") (pinfunction "3_3") (pintype "passive"))
    )
    (net (code "114") (name "unconnected-(JP2-Pad4)") (class "Default")
      (node (ref "JP2") (pin "4") (pinfunction "4_4") (pintype "passive"))
    )
    (net (code "115") (name "unconnected-(JP2-Pad5)") (class "Default")
      (node (ref "JP2") (pin "5") (pinfunction "5_5") (pintype "passive"))
    )
    (net (code "116") (name "unconnected-(JP2-Pad7)") (class "Default")
      (node (ref "JP2") (pin "7") (pinfunction "7_7") (pintype "passive"))
    )
    (net (code "117") (name "unconnected-(JP2-Pad8)") (class "Default")
      (node (ref "JP2") (pin "8") (pinfunction "8_8") (pintype "passive"))
    )
    (net (code "118") (name "unconnected-(JP2-Pad9)") (class "Default")
      (node (ref "JP2") (pin "9") (pinfunction "9_9") (pintype "passive"))
    )
    (net (code "119") (name "unconnected-(JP2-Pad10)") (class "Default")
      (node (ref "JP2") (pin "10") (pinfunction "10_10") (pintype "passive"))
    )
    (net (code "120") (name "unconnected-(JP2-Pad11)") (class "Default")
      (node (ref "JP2") (pin "11") (pinfunction "11_11") (pintype "passive"))
    )
    (net (code "121") (name "unconnected-(JP2-Pad13)") (class "Default")
      (node (ref "JP2") (pin "13") (pinfunction "13_13") (pintype "passive"))
    )
    (net (code "122") (name "unconnected-(JP2-Pad15)") (class "Default")
      (node (ref "JP2") (pin "15") (pinfunction "15_15") (pintype "passive"))
    )
    (net (code "123") (name "unconnected-(JP2-Pad17)") (class "Default")
      (node (ref "JP2") (pin "17") (pinfunction "17_17") (pintype "passive"))
    )
    (net (code "124") (name "unconnected-(JP2-Pad19)") (class "Default")
      (node (ref "JP2") (pin "19") (pinfunction "19_19") (pintype "passive"))
    )
    (net (code "125") (name "unconnected-(JP2-Pad20)") (class "Default")
      (node (ref "JP2") (pin "20") (pinfunction "20_20") (pintype "passive"))
    )
    (net (code "126") (name "unconnected-(RN5G-1-Pad7)") (class "Default")
      (node (ref "RN5") (pin "7") (pinfunction "1_7") (pintype "passive"))
    )
    (net (code "127") (name "unconnected-(RN5G-2-Pad8)") (class "Default")
      (node (ref "RN5") (pin "8") (pinfunction "2_8") (pintype "passive"))
    )
  )
)
